# Sheet1.net
KiCad netlist of a schematic drawn in Altium Designer
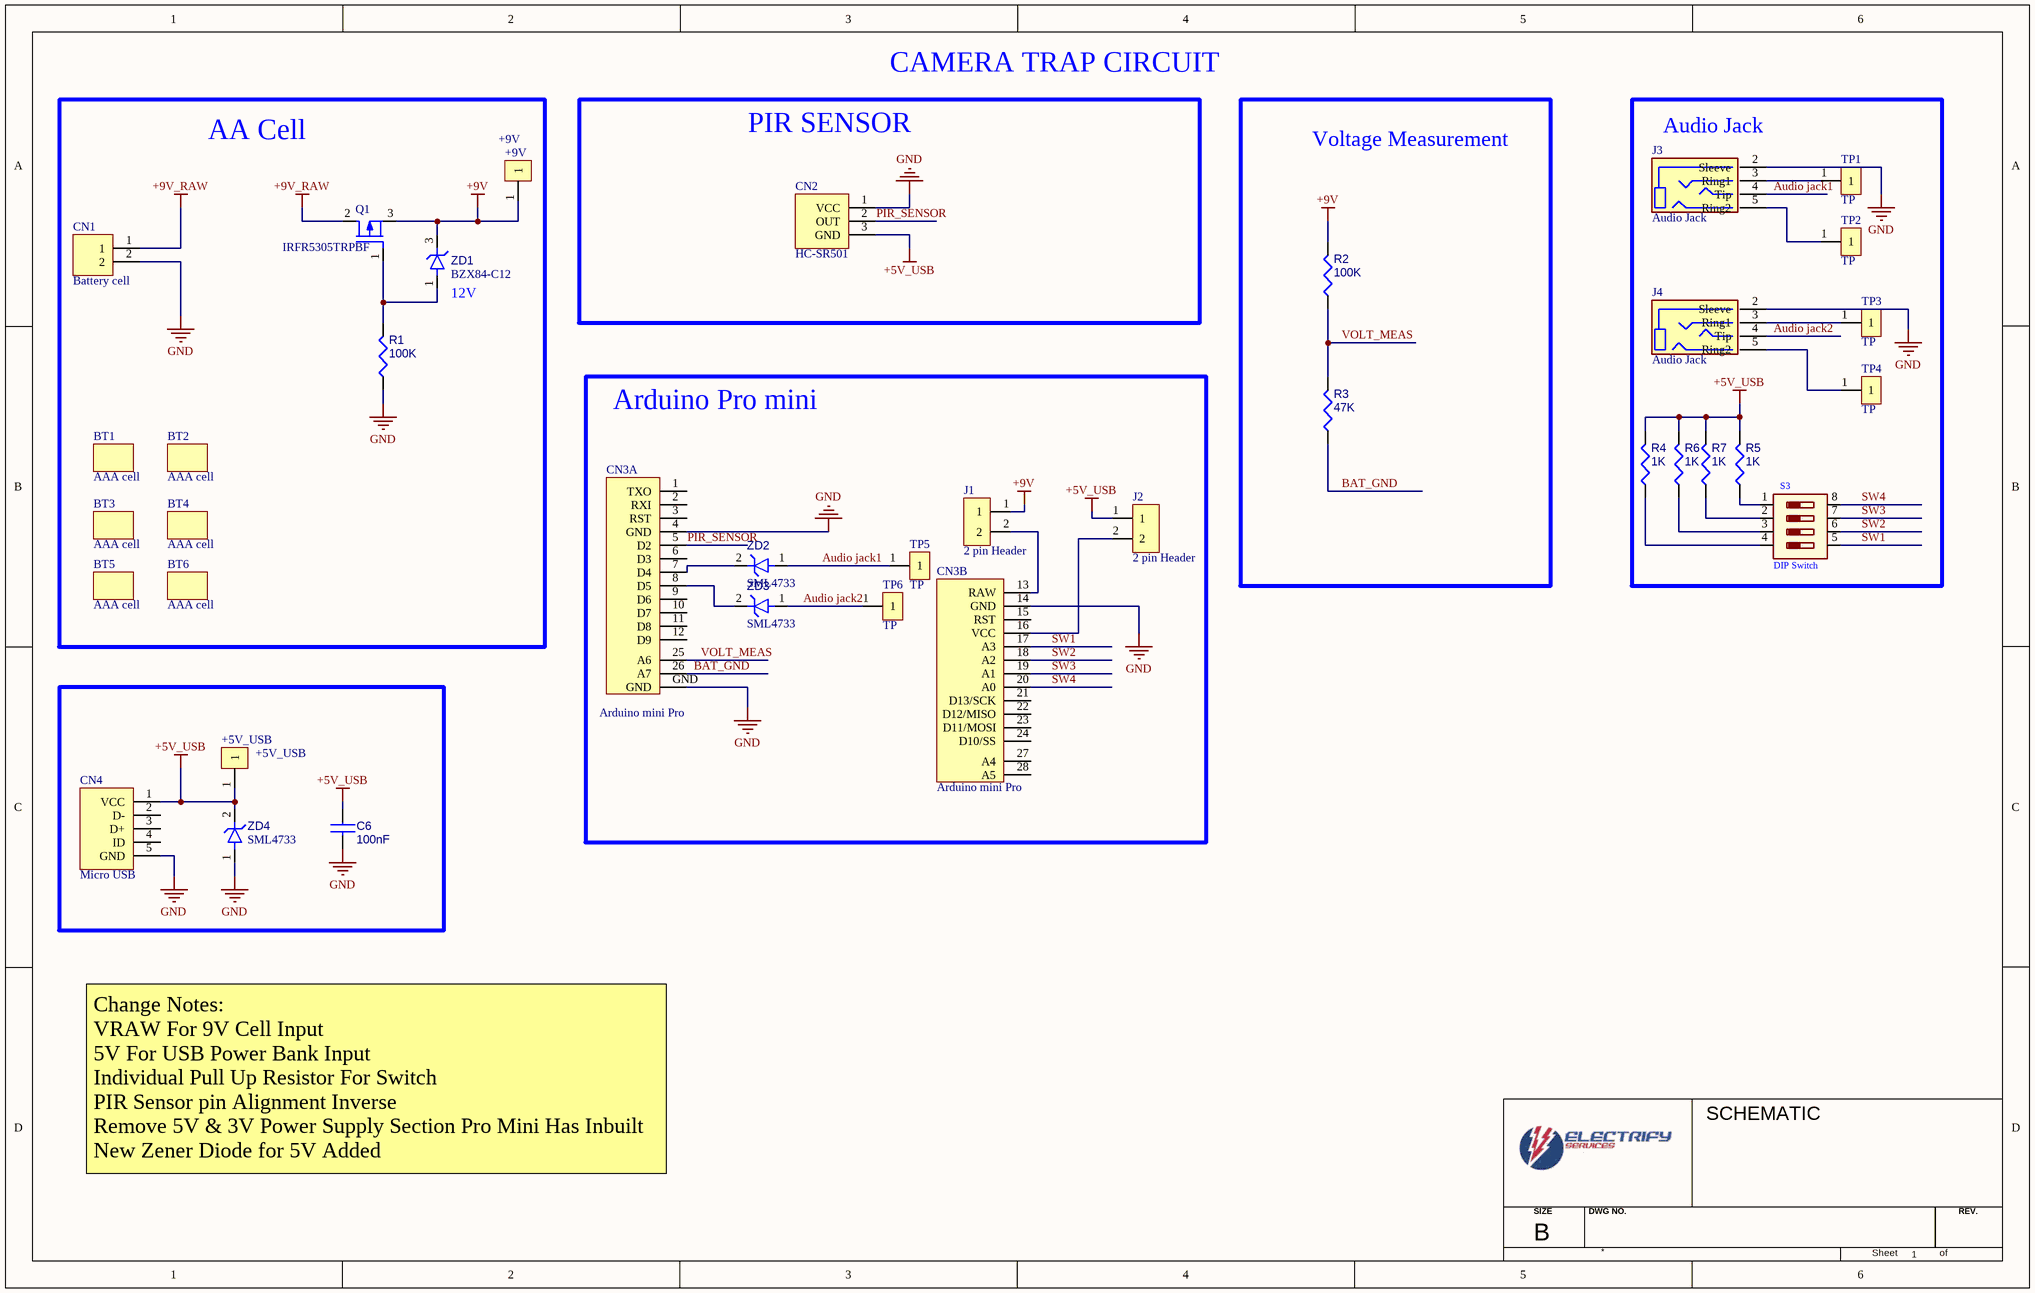
[diagram p0: Sheet1.SchDoc]

(export (version "E")
  (design (tool "Eeschema 10.0.6"))
  (components
    (comp (ref "+5V_USB") (value "+5V_USB") (footprint "TP_SMD") (libsource (lib "Schlib1") (part "TP")))
    (comp (ref "+9V") (value "+9V") (footprint "TP_SMD") (libsource (lib "Schlib1") (part "TP")))
    (comp (ref "BT1") (value "AAA cell") (libsource (lib "Schlib1") (part "Battery Holder")))
    (comp (ref "BT2") (value "AAA cell") (libsource (lib "Schlib1") (part "Battery Holder")))
    (comp (ref "BT3") (value "AAA cell") (libsource (lib "Schlib1") (part "Battery Holder")))
    (comp (ref "BT4") (value "AAA cell") (libsource (lib "Schlib1") (part "Battery Holder")))
    (comp (ref "BT5") (value "AAA cell") (libsource (lib "Schlib1") (part "Battery Holder")))
    (comp (ref "BT6") (value "AAA cell") (libsource (lib "Schlib1") (part "Battery Holder")))
    (comp (ref "C6")
      (value "100nF")
      (footprint "CAP_0603_MANUAL")
      (description "100nF 104 0603 (1608 metric) 50V X7R MLCC")
      (libsource (lib "Schlib1") (part "CAP CER 100nF 50V X7R 0603"))
    )
    (comp (ref "CN1")
      (value "Battery cell")
      (footprint "BAT_AAA")
      (description "6x AAA cell")
      (libsource (lib "Schlib1") (part "Battery Cell"))
    )
    (comp (ref "CN2")
      (value "HC-SR501")
      (footprint "PIR-SR501")
      (description "PIR Motion Detection Sensor HC-SR501")
      (libsource (lib "Schlib1") (part "PIR Motion Detection Sensor HC-SR501"))
    )
    (comp (ref "CN3")
      (value "Arduino mini Pro")
      (footprint "Arduino pro mini")
      (description "Pro Mini - ATMEGA 328P - 5V 16Mhz - Compatible Board")
      (libsource (lib "Schlib1") (part "Arduino mini Pro"))
    )
    (comp (ref "CN4")
      (value "Micro USB")
      (footprint "AMPHENOL_10118194-0001LF")
      (description "MicroUSB Connector with through hole")
      (libsource (lib "Schlib1") (part "Micro USB Connector"))
    )
    (comp (ref "J1")
      (value "2 pin Header")
      (footprint "2Pin_Header_2.54mmpitch")
      (libsource (lib "") (part "2 pin Header_1"))
    )
    (comp (ref "J2")
      (value "2 pin Header")
      (footprint "2Pin_Header_2.54mmpitch")
      (libsource (lib "Schlib1") (part "2 pin Header"))
    )
    (comp (ref "J3")
      (value "Audio Jack")
      (footprint "Audio JAck")
      (description "Stereo Socket 3.5mm PCB Mount SMD")
      (libsource (lib "Schlib1") (part "Stereo Socket 3.5mm PCB Mount SMD"))
    )
    (comp (ref "J4")
      (value "Audio Jack")
      (footprint "Audio JAck")
      (description "Stereo Socket 3.5mm PCB Mount SMD")
      (libsource (lib "Schlib1") (part "Stereo Socket 3.5mm PCB Mount SMD"))
    )
    (comp (ref "Q1")
      (value "IRFR5305TRPBF")
      (footprint "TO-252")
      (description "IRFR5305TRPBF (31A 55V) IRFR5305 TO252 P-CH MOSFET")
      (fields (field (name "MANUFACTURER") "Infineon Technologies"))
      (libsource (lib "Schlib1") (part "MOSFET P-CH 55V 31A TO252"))
    )
    (comp (ref "R1")
      (value "100K")
      (footprint "RES_0603_MANUAL")
      (description "47K 1% 0603")
      (libsource (lib "Schlib1") (part "RES 100K OHM 1% 0603"))
    )
    (comp (ref "R2")
      (value "100K")
      (footprint "RES_0603_MANUAL")
      (description "100K 1% 0603")
      (libsource (lib "Schlib1") (part "100K 1% 0603"))
    )
    (comp (ref "R3")
      (value "47K")
      (footprint "RES_0603_MANUAL")
      (description "47K 1% 0603")
      (libsource (lib "Schlib1") (part "RES 47K OHM 1% 0603"))
    )
    (comp (ref "R4")
      (value "1K")
      (footprint "RES_0603_MANUAL")
      (description "100K 1% 0603")
      (libsource (lib "Schlib1") (part "1K 1% 0603"))
    )
    (comp (ref "R5")
      (value "1K")
      (footprint "RES_0603_MANUAL")
      (description "100K 1% 0603")
      (libsource (lib "Schlib1") (part "1K 1% 0603"))
    )
    (comp (ref "R6")
      (value "1K")
      (footprint "RES_0603_MANUAL")
      (description "100K 1% 0603")
      (libsource (lib "Schlib1") (part "1K 1% 0603"))
    )
    (comp (ref "R7")
      (value "1K")
      (footprint "RES_0603_MANUAL")
      (description "100K 1% 0603")
      (libsource (lib "Schlib1") (part "1K 1% 0603"))
    )
    (comp (ref "S3")
      (value "DIP Switch")
      (footprint "DIP Switch")
      (description "4 Way 2.54MM DIP switch")
      (libsource (lib "Schlib1") (part "SPST DIP Switch"))
    )
    (comp (ref "TP1") (value "TP") (footprint "Tp") (libsource (lib "") (part "TP_1")))
    (comp (ref "TP2") (value "TP") (footprint "Tp") (libsource (lib "") (part "TP_1")))
    (comp (ref "TP3") (value "TP") (footprint "Tp") (libsource (lib "") (part "TP_1")))
    (comp (ref "TP4") (value "TP") (footprint "Tp") (libsource (lib "") (part "TP_1")))
    (comp (ref "TP5") (value "TP") (footprint "Tp") (libsource (lib "") (part "TP_1")))
    (comp (ref "TP6") (value "TP") (footprint "Tp") (libsource (lib "") (part "TP_1")))
    (comp (ref "ZD1")
      (value "BZX84-C12")
      (footprint "SOT-23")
      (description "BZX84-C12 NXP 12V 250mW SOT23 Zener Diode")
      (libsource (lib "Schlib1") (part "BZX84-C12 NXP 12V 250mW SOT23"))
    )
    (comp (ref "ZD2")
      (value "SML4733")
      (footprint "DO-214AC_SMA")
      (description "SML4733 5.1V 1W Zener Diode DO-214AC (SMA) SMD")
      (libsource (lib "Schlib1") (part "SML4733 5.1V 1W Zener Diode DO-214AC"))
    )
    (comp (ref "ZD3")
      (value "SML4733")
      (footprint "DO-214AC_SMA")
      (description "SML4733 5.1V 1W Zener Diode DO-214AC (SMA) SMD")
      (libsource (lib "Schlib1") (part "SML4733 5.1V 1W Zener Diode DO-214AC"))
    )
    (comp (ref "ZD4")
      (value "SML4733")
      (footprint "DO-214AC_SMA")
      (description "SML4733 5.1V 1W Zener Diode DO-214AC (SMA) SMD")
      (libsource (lib "Schlib1") (part "SML4733 5.1V 1W Zener Diode DO-214AC"))
    )
  )
  (nets
    (net (code "1") (name "+5V_USB") (class "Default")
      (node (ref "+5V_USB") (pin "1") (pinfunction "1_1") (pintype "passive"))
      (node (ref "C6") (pin "1") (pinfunction "1_1") (pintype "passive"))
      (node (ref "CN2") (pin "3") (pinfunction "GND_3") (pintype "passive"))
      (node (ref "CN4") (pin "1") (pinfunction "VCC_1") (pintype "passive"))
      (node (ref "J2") (pin "1") (pinfunction "1_1") (pintype "passive"))
      (node (ref "R4") (pin "2") (pinfunction "2_2") (pintype "passive"))
      (node (ref "R5") (pin "2") (pinfunction "2_2") (pintype "passive"))
      (node (ref "R6") (pin "2") (pinfunction "2_2") (pintype "passive"))
      (node (ref "R7") (pin "2") (pinfunction "2_2") (pintype "passive"))
      (node (ref "ZD4") (pin "2") (pinfunction "C_2") (pintype "passive"))
    )
    (net (code "2") (name "+9V") (class "Default")
      (node (ref "+9V") (pin "1") (pinfunction "1_1") (pintype "passive"))
      (node (ref "J1") (pin "1") (pinfunction "1_1") (pintype "passive"))
      (node (ref "Q1") (pin "3") (pinfunction "SOURCE_3") (pintype "passive"))
      (node (ref "R2") (pin "2") (pinfunction "2_2") (pintype "passive"))
      (node (ref "ZD1") (pin "3") (pinfunction "C_3") (pintype "passive"))
    )
    (net (code "3") (name "+9V_RAW") (class "Default")
      (node (ref "CN1") (pin "1") (pinfunction "1_1") (pintype "passive"))
      (node (ref "Q1") (pin "2") (pinfunction "DRAIN_2") (pintype "passive"))
    )
    (net (code "4") (name "/Audio jack1") (class "Default")
      (node (ref "J3") (pin "4") (pinfunction "Tip_4") (pintype "passive"))
      (node (ref "TP5") (pin "1") (pinfunction "1_1") (pintype "passive"))
      (node (ref "ZD2") (pin "1") (pinfunction "A_1") (pintype "passive"))
    )
    (net (code "5") (name "/Audio jack2") (class "Default")
      (node (ref "J4") (pin "4") (pinfunction "Tip_4") (pintype "passive"))
      (node (ref "TP6") (pin "1") (pinfunction "1_1") (pintype "passive"))
      (node (ref "ZD3") (pin "1") (pinfunction "A_1") (pintype "passive"))
    )
    (net (code "6") (name "/BAT_GND") (class "Default")
      (node (ref "CN3") (pin "26") (pinfunction "A7_26") (pintype "passive"))
      (node (ref "R3") (pin "1") (pinfunction "1_1") (pintype "passive"))
    )
    (net (code "7") (name "/PIR_SENSOR") (class "Default")
      (node (ref "CN2") (pin "2") (pinfunction "OUT_2") (pintype "passive"))
      (node (ref "CN3") (pin "5") (pinfunction "D2_5") (pintype "passive"))
    )
    (net (code "8") (name "/SW1") (class "Default")
      (node (ref "CN3") (pin "17") (pinfunction "A3_17") (pintype "passive"))
      (node (ref "S3") (pin "5") (pinfunction "5_5") (pintype "passive"))
    )
    (net (code "9") (name "/SW2") (class "Default")
      (node (ref "CN3") (pin "18") (pinfunction "A2_18") (pintype "passive"))
      (node (ref "S3") (pin "6") (pinfunction "6_6") (pintype "passive"))
    )
    (net (code "10") (name "/SW3") (class "Default")
      (node (ref "CN3") (pin "19") (pinfunction "A1_19") (pintype "passive"))
      (node (ref "S3") (pin "7") (pinfunction "7_7") (pintype "passive"))
    )
    (net (code "11") (name "/SW4") (class "Default")
      (node (ref "CN3") (pin "20") (pinfunction "A0_20") (pintype "passive"))
      (node (ref "S3") (pin "8") (pinfunction "8_8") (pintype "passive"))
    )
    (net (code "12") (name "/VOLT_MEAS") (class "Default")
      (node (ref "CN3") (pin "25") (pinfunction "A6_25") (pintype "passive"))
      (node (ref "R2") (pin "1") (pinfunction "1_1") (pintype "passive"))
      (node (ref "R3") (pin "2") (pinfunction "2_2") (pintype "passive"))
    )
    (net (code "13") (name "GND") (class "Default")
      (node (ref "C6") (pin "2") (pinfunction "2_2") (pintype "passive"))
      (node (ref "CN1") (pin "2") (pinfunction "2_2") (pintype "passive"))
      (node (ref "CN2") (pin "1") (pinfunction "VCC_1") (pintype "passive"))
      (node (ref "CN3") (pin "14") (pinfunction "GND_14") (pintype "passive"))
      (node (ref "CN3") (pin "4") (pinfunction "GND_4") (pintype "passive"))
      (node (ref "CN3") (pin "GND") (pinfunction "GND_GND") (pintype "passive"))
      (node (ref "CN4") (pin "5") (pinfunction "GND_5") (pintype "passive"))
      (node (ref "J3") (pin "2") (pinfunction "Sleeve_2") (pintype "passive"))
      (node (ref "J4") (pin "2") (pinfunction "Sleeve_2") (pintype "passive"))
      (node (ref "R1") (pin "1") (pinfunction "1_1") (pintype "passive"))
      (node (ref "ZD4") (pin "1") (pinfunction "A_1") (pintype "passive"))
    )
    (net (code "14") (name "Net-(CN3A-D4)") (class "Default")
      (node (ref "CN3") (pin "7") (pinfunction "D4_7") (pintype "passive"))
      (node (ref "ZD2") (pin "2") (pinfunction "C_2") (pintype "passive"))
    )
    (net (code "15") (name "Net-(CN3A-D5)") (class "Default")
      (node (ref "CN3") (pin "8") (pinfunction "D5_8") (pintype "passive"))
      (node (ref "ZD3") (pin "2") (pinfunction "C_2") (pintype "passive"))
    )
    (net (code "16") (name "Net-(CN3B-RAW)") (class "Default")
      (node (ref "CN3") (pin "13") (pinfunction "RAW_13") (pintype "passive"))
      (node (ref "J1") (pin "2") (pinfunction "2_2") (pintype "passive"))
    )
    (net (code "17") (name "Net-(CN3B-VCC)") (class "Default")
      (node (ref "CN3") (pin "16") (pinfunction "VCC_16") (pintype "passive"))
      (node (ref "J2") (pin "2") (pinfunction "2_2") (pintype "passive"))
    )
    (net (code "18") (name "Net-(J3-Ring1)") (class "Default")
      (node (ref "J3") (pin "3") (pinfunction "Ring1_3") (pintype "passive"))
      (node (ref "TP1") (pin "1") (pinfunction "1_1") (pintype "passive"))
    )
    (net (code "19") (name "Net-(J3-Ring2)") (class "Default")
      (node (ref "J3") (pin "5") (pinfunction "Ring2_5") (pintype "passive"))
      (node (ref "TP2") (pin "1") (pinfunction "1_1") (pintype "passive"))
    )
    (net (code "20") (name "Net-(J4-Ring1)") (class "Default")
      (node (ref "J4") (pin "3") (pinfunction "Ring1_3") (pintype "passive"))
      (node (ref "TP3") (pin "1") (pinfunction "1_1") (pintype "passive"))
    )
    (net (code "21") (name "Net-(J4-Ring2)") (class "Default")
      (node (ref "J4") (pin "5") (pinfunction "Ring2_5") (pintype "passive"))
      (node (ref "TP4") (pin "1") (pinfunction "1_1") (pintype "passive"))
    )
    (net (code "22") (name "Net-(Q1-GATE)") (class "Default")
      (node (ref "Q1") (pin "1") (pinfunction "GATE_1") (pintype "passive"))
      (node (ref "R1") (pin "2") (pinfunction "2_2") (pintype "passive"))
      (node (ref "ZD1") (pin "1") (pinfunction "A_1") (pintype "passive"))
    )
    (net (code "23") (name "Net-(R4-Pad1)") (class "Default")
      (node (ref "R4") (pin "1") (pinfunction "1_1") (pintype "passive"))
      (node (ref "S3") (pin "4") (pinfunction "4_4") (pintype "passive"))
    )
    (net (code "24") (name "Net-(R5-Pad1)") (class "Default")
      (node (ref "R5") (pin "1") (pinfunction "1_1") (pintype "passive"))
      (node (ref "S3") (pin "1") (pinfunction "1_1") (pintype "passive"))
    )
    (net (code "25") (name "Net-(R6-Pad1)") (class "Default")
      (node (ref "R6") (pin "1") (pinfunction "1_1") (pintype "passive"))
      (node (ref "S3") (pin "3") (pinfunction "3_3") (pintype "passive"))
    )
    (net (code "26") (name "Net-(R7-Pad1)") (class "Default")
      (node (ref "R7") (pin "1") (pinfunction "1_1") (pintype "passive"))
      (node (ref "S3") (pin "2") (pinfunction "2_2") (pintype "passive"))
    )
    (net (code "27") (name "unconnected-(CN3A-D3-Pad6)") (class "Default")
      (node (ref "CN3") (pin "6") (pinfunction "D3_6") (pintype "passive"))
    )
    (net (code "28") (name "unconnected-(CN3A-D6-Pad9)") (class "Default")
      (node (ref "CN3") (pin "9") (pinfunction "D6_9") (pintype "passive"))
    )
    (net (code "29") (name "unconnected-(CN3A-D7-Pad10)") (class "Default")
      (node (ref "CN3") (pin "10") (pinfunction "D7_10") (pintype "passive"))
    )
    (net (code "30") (name "unconnected-(CN3A-D8-Pad11)") (class "Default")
      (node (ref "CN3") (pin "11") (pinfunction "D8_11") (pintype "passive"))
    )
    (net (code "31") (name "unconnected-(CN3A-D9-Pad12)") (class "Default")
      (node (ref "CN3") (pin "12") (pinfunction "D9_12") (pintype "passive"))
    )
    (net (code "32") (name "unconnected-(CN3A-RST-Pad3)") (class "Default")
      (node (ref "CN3") (pin "3") (pinfunction "RST_3") (pintype "passive"))
    )
    (net (code "33") (name "unconnected-(CN3A-RXI-Pad2)") (class "Default")
      (node (ref "CN3") (pin "2") (pinfunction "RXI_2") (pintype "passive"))
    )
    (net (code "34") (name "unconnected-(CN3A-TXO-Pad1)") (class "Default")
      (node (ref "CN3") (pin "1") (pinfunction "TXO_1") (pintype "passive"))
    )
    (net (code "35") (name "unconnected-(CN3B-A4-Pad27)") (class "Default")
      (node (ref "CN3") (pin "27") (pinfunction "A4_27") (pintype "passive"))
    )
    (net (code "36") (name "unconnected-(CN3B-A5-Pad28)") (class "Default")
      (node (ref "CN3") (pin "28") (pinfunction "A5_28") (pintype "passive"))
    )
    (net (code "37") (name "unconnected-(CN3B-D10{slash}SS-Pad24)") (class "Default")
      (node (ref "CN3") (pin "24") (pinfunction "D10/SS_24") (pintype "passive"))
    )
    (net (code "38") (name "unconnected-(CN3B-D11{slash}MOSI-Pad23)") (class "Default")
      (node (ref "CN3") (pin "23") (pinfunction "D11/MOSI_23") (pintype "passive"))
    )
    (net (code "39") (name "unconnected-(CN3B-D12{slash}MISO-Pad22)") (class "Default")
      (node (ref "CN3") (pin "22") (pinfunction "D12/MISO_22") (pintype "passive"))
    )
    (net (code "40") (name "unconnected-(CN3B-D13{slash}SCK-Pad21)") (class "Default")
      (node (ref "CN3") (pin "21") (pinfunction "D13/SCK_21") (pintype "passive"))
    )
    (net (code "41") (name "unconnected-(CN3B-RST-Pad15)") (class "Default")
      (node (ref "CN3") (pin "15") (pinfunction "RST_15") (pintype "passive"))
    )
    (net (code "42") (name "unconnected-(CN4-D+-Pad3)") (class "Default")
      (node (ref "CN4") (pin "3") (pinfunction "D+_3") (pintype "passive"))
    )
    (net (code "43") (name "unconnected-(CN4-D--Pad2)") (class "Default")
      (node (ref "CN4") (pin "2") (pinfunction "D-_2") (pintype "passive"))
    )
    (net (code "44") (name "unconnected-(CN4-ID-Pad4)") (class "Default")
      (node (ref "CN4") (pin "4") (pinfunction "ID_4") (pintype "passive"))
    )
  )
)
